# SCH_CubeNixie_2024-07-25.net
KiCad netlist of a schematic drawn in EasyEDA
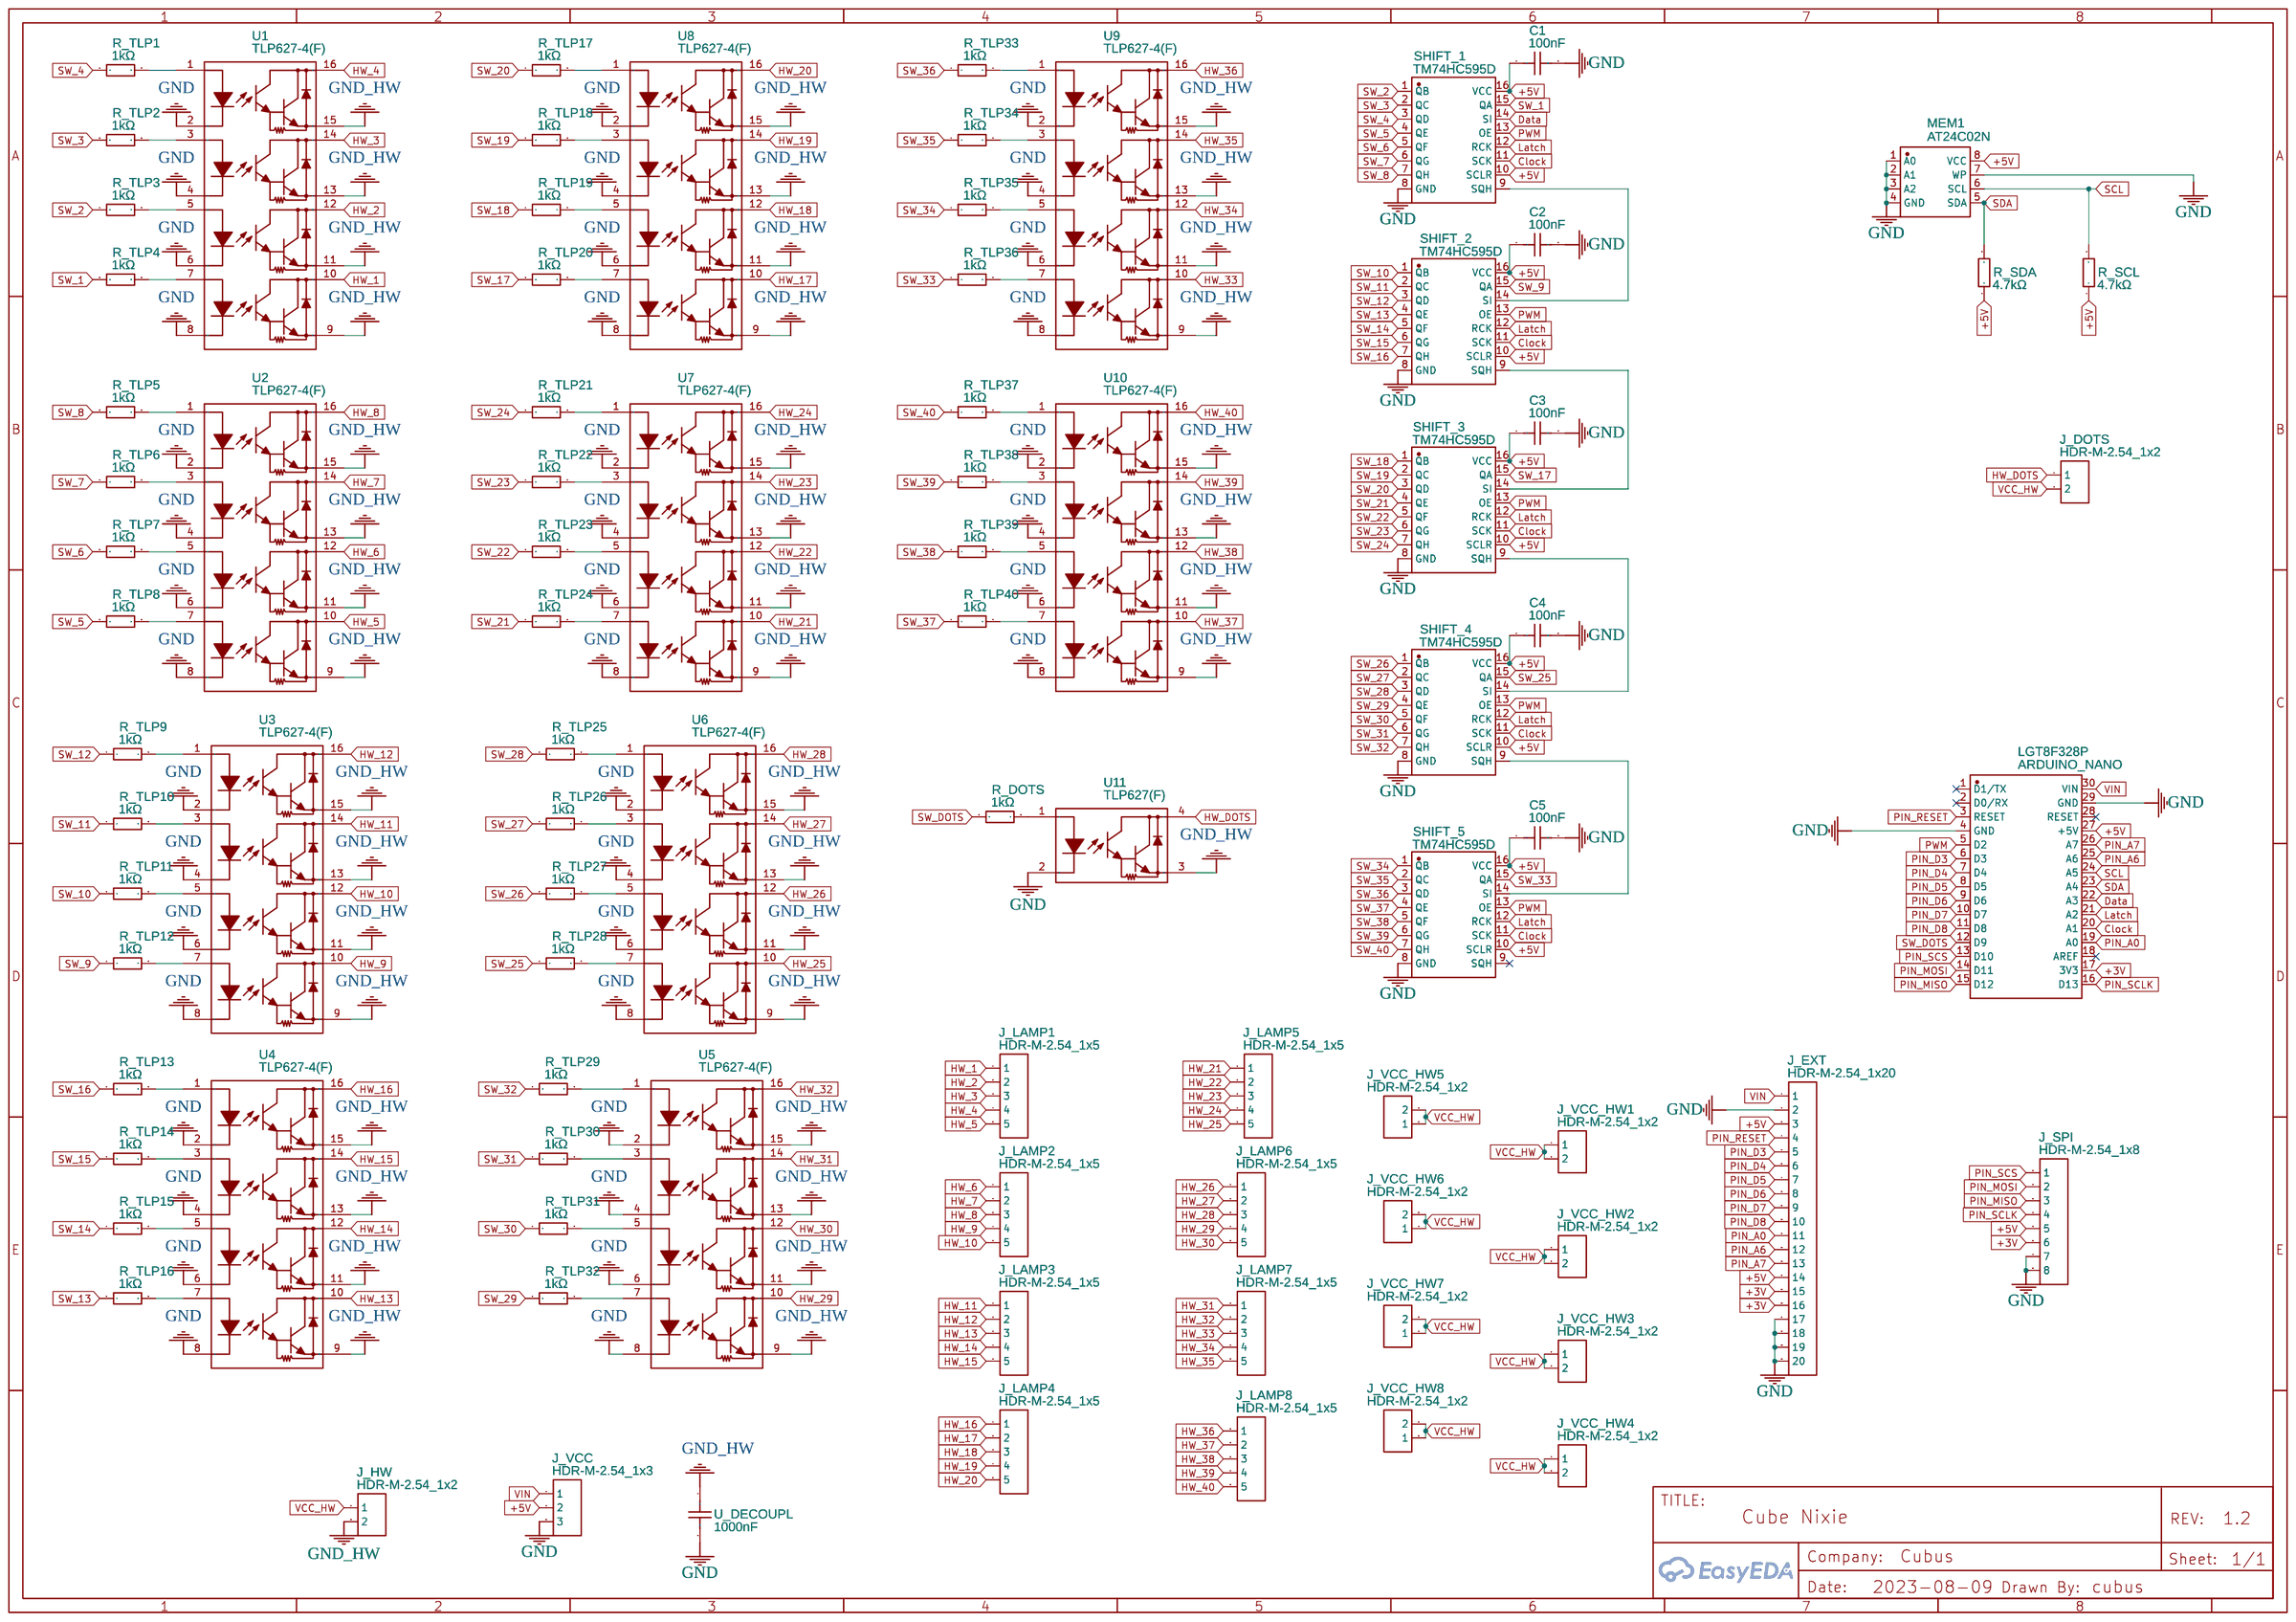
[diagram p0: schematic sheet]

(export (version "E")
  (design (tool "Eeschema 10.0.6"))
  (components
    (comp (ref "C1")
      (value "100nF")
      (fields (field (name "Manufacturer Part") "C3216X7R2A104M160AA") (field (name "Manufacturer") "TDK"))
      (libsource (lib "") (part "C3216X7R2A104M160AA"))
    )
    (comp (ref "C2")
      (value "100nF")
      (fields (field (name "Manufacturer Part") "C3216X7R2A104M160AA") (field (name "Manufacturer") "TDK"))
      (libsource (lib "") (part "C3216X7R2A104M160AA"))
    )
    (comp (ref "C3")
      (value "100nF")
      (fields (field (name "Manufacturer Part") "C3216X7R2A104M160AA") (field (name "Manufacturer") "TDK"))
      (libsource (lib "") (part "C3216X7R2A104M160AA"))
    )
    (comp (ref "C4")
      (value "100nF")
      (fields (field (name "Manufacturer Part") "C3216X7R2A104M160AA") (field (name "Manufacturer") "TDK"))
      (libsource (lib "") (part "C3216X7R2A104M160AA"))
    )
    (comp (ref "C5")
      (value "100nF")
      (fields (field (name "Manufacturer Part") "C3216X7R2A104M160AA") (field (name "Manufacturer") "TDK"))
      (libsource (lib "") (part "C3216X7R2A104M160AA"))
    )
    (comp (ref "J_DOTS") (value "HDR-M-2.54_1x2") (libsource (lib "") (part "HDR-M-2.54_1x2_3")))
    (comp (ref "J_EXT") (value "HDR-M-2.54_1x20") (libsource (lib "") (part "HDR-M-2.54_1x20")))
    (comp (ref "J_HW") (value "HDR-M-2.54_1x2") (libsource (lib "") (part "HDR-M-2.54_1x2_2")))
    (comp (ref "J_LAMP1") (value "HDR-M-2.54_1x5") (libsource (lib "") (part "HDR-M-2.54_1x5")))
    (comp (ref "J_LAMP2") (value "HDR-M-2.54_1x5") (libsource (lib "") (part "HDR-M-2.54_1x5")))
    (comp (ref "J_LAMP3") (value "HDR-M-2.54_1x5") (libsource (lib "") (part "HDR-M-2.54_1x5")))
    (comp (ref "J_LAMP4") (value "HDR-M-2.54_1x5") (libsource (lib "") (part "HDR-M-2.54_1x5")))
    (comp (ref "J_LAMP5") (value "HDR-M-2.54_1x5") (libsource (lib "") (part "HDR-M-2.54_1x5")))
    (comp (ref "J_LAMP6") (value "HDR-M-2.54_1x5") (libsource (lib "") (part "HDR-M-2.54_1x5")))
    (comp (ref "J_LAMP7") (value "HDR-M-2.54_1x5") (libsource (lib "") (part "HDR-M-2.54_1x5")))
    (comp (ref "J_LAMP8") (value "HDR-M-2.54_1x5") (libsource (lib "") (part "HDR-M-2.54_1x5")))
    (comp (ref "J_SPI") (value "HDR-M-2.54_1x8") (libsource (lib "") (part "HDR-M-2.54_1x8")))
    (comp (ref "J_VCC") (value "HDR-M-2.54_1x3") (libsource (lib "") (part "HDR-M-2.54_1x3")))
    (comp (ref "J_VCC_HW1") (value "HDR-M-2.54_1x2") (libsource (lib "") (part "HDR-M-2.54_1x2_1")))
    (comp (ref "J_VCC_HW2") (value "HDR-M-2.54_1x2") (libsource (lib "") (part "HDR-M-2.54_1x2_1")))
    (comp (ref "J_VCC_HW3") (value "HDR-M-2.54_1x2") (libsource (lib "") (part "HDR-M-2.54_1x2_1")))
    (comp (ref "J_VCC_HW4") (value "HDR-M-2.54_1x2") (libsource (lib "") (part "HDR-M-2.54_1x2_1")))
    (comp (ref "J_VCC_HW5") (value "HDR-M-2.54_1x2") (libsource (lib "") (part "HDR-M-2.54_1x2")))
    (comp (ref "J_VCC_HW6") (value "HDR-M-2.54_1x2") (libsource (lib "") (part "HDR-M-2.54_1x2")))
    (comp (ref "J_VCC_HW7") (value "HDR-M-2.54_1x2") (libsource (lib "") (part "HDR-M-2.54_1x2")))
    (comp (ref "J_VCC_HW8") (value "HDR-M-2.54_1x2") (libsource (lib "") (part "HDR-M-2.54_1x2")))
    (comp (ref "LGT8F328P") (value "ARDUINO_NANO") (libsource (lib "") (part "ARDUINO_NANO")))
    (comp (ref "MEM1")
      (value "AT24C02N")
      (fields (field (name "Manufacturer") "HGSEMI"))
      (libsource (lib "") (part "AT24C02N"))
    )
    (comp (ref "R_DOTS")
      (value "1kΩ")
      (fields (field (name "Manufacturer Part") "ERJ6ENF1001V") (field (name "Manufacturer") "PANASONIC(松下)"))
      (libsource (lib "") (part "ERJ-6ENF1001V_1"))
    )
    (comp (ref "R_SCL")
      (value "4.7kΩ")
      (fields (field (name "Manufacturer Part") "RMC04024K7JN") (field (name "Manufacturer") "Tyohm(幸亚电阻)"))
      (libsource (lib "") (part "RMC04024.7K5%N"))
    )
    (comp (ref "R_SDA")
      (value "4.7kΩ")
      (fields (field (name "Manufacturer Part") "RMC04024K7JN") (field (name "Manufacturer") "Tyohm(幸亚电阻)"))
      (libsource (lib "") (part "RMC04024.7K5%N_1"))
    )
    (comp (ref "R_TLP1")
      (value "1kΩ")
      (fields (field (name "Manufacturer Part") "ERJ6ENF1001V") (field (name "Manufacturer") "PANASONIC(松下)"))
      (libsource (lib "") (part "ERJ-6ENF1001V"))
    )
    (comp (ref "R_TLP2")
      (value "1kΩ")
      (fields (field (name "Manufacturer Part") "ERJ6ENF1001V") (field (name "Manufacturer") "PANASONIC(松下)"))
      (libsource (lib "") (part "ERJ-6ENF1001V"))
    )
    (comp (ref "R_TLP3")
      (value "1kΩ")
      (fields (field (name "Manufacturer Part") "ERJ6ENF1001V") (field (name "Manufacturer") "PANASONIC(松下)"))
      (libsource (lib "") (part "ERJ-6ENF1001V"))
    )
    (comp (ref "R_TLP4")
      (value "1kΩ")
      (fields (field (name "Manufacturer Part") "ERJ6ENF1001V") (field (name "Manufacturer") "PANASONIC(松下)"))
      (libsource (lib "") (part "ERJ-6ENF1001V"))
    )
    (comp (ref "R_TLP5")
      (value "1kΩ")
      (fields (field (name "Manufacturer Part") "ERJ6ENF1001V") (field (name "Manufacturer") "PANASONIC(松下)"))
      (libsource (lib "") (part "ERJ-6ENF1001V"))
    )
    (comp (ref "R_TLP6")
      (value "1kΩ")
      (fields (field (name "Manufacturer Part") "ERJ6ENF1001V") (field (name "Manufacturer") "PANASONIC(松下)"))
      (libsource (lib "") (part "ERJ-6ENF1001V"))
    )
    (comp (ref "R_TLP7")
      (value "1kΩ")
      (fields (field (name "Manufacturer Part") "ERJ6ENF1001V") (field (name "Manufacturer") "PANASONIC(松下)"))
      (libsource (lib "") (part "ERJ-6ENF1001V"))
    )
    (comp (ref "R_TLP8")
      (value "1kΩ")
      (fields (field (name "Manufacturer Part") "ERJ6ENF1001V") (field (name "Manufacturer") "PANASONIC(松下)"))
      (libsource (lib "") (part "ERJ-6ENF1001V"))
    )
    (comp (ref "R_TLP9")
      (value "1kΩ")
      (fields (field (name "Manufacturer Part") "ERJ6ENF1001V") (field (name "Manufacturer") "PANASONIC(松下)"))
      (libsource (lib "") (part "ERJ-6ENF1001V"))
    )
    (comp (ref "R_TLP10")
      (value "1kΩ")
      (fields (field (name "Manufacturer Part") "ERJ6ENF1001V") (field (name "Manufacturer") "PANASONIC(松下)"))
      (libsource (lib "") (part "ERJ-6ENF1001V"))
    )
    (comp (ref "R_TLP11")
      (value "1kΩ")
      (fields (field (name "Manufacturer Part") "ERJ6ENF1001V") (field (name "Manufacturer") "PANASONIC(松下)"))
      (libsource (lib "") (part "ERJ-6ENF1001V"))
    )
    (comp (ref "R_TLP12")
      (value "1kΩ")
      (fields (field (name "Manufacturer Part") "ERJ6ENF1001V") (field (name "Manufacturer") "PANASONIC(松下)"))
      (libsource (lib "") (part "ERJ-6ENF1001V"))
    )
    (comp (ref "R_TLP13")
      (value "1kΩ")
      (fields (field (name "Manufacturer Part") "ERJ6ENF1001V") (field (name "Manufacturer") "PANASONIC(松下)"))
      (libsource (lib "") (part "ERJ-6ENF1001V"))
    )
    (comp (ref "R_TLP14")
      (value "1kΩ")
      (fields (field (name "Manufacturer Part") "ERJ6ENF1001V") (field (name "Manufacturer") "PANASONIC(松下)"))
      (libsource (lib "") (part "ERJ-6ENF1001V"))
    )
    (comp (ref "R_TLP15")
      (value "1kΩ")
      (fields (field (name "Manufacturer Part") "ERJ6ENF1001V") (field (name "Manufacturer") "PANASONIC(松下)"))
      (libsource (lib "") (part "ERJ-6ENF1001V"))
    )
    (comp (ref "R_TLP16")
      (value "1kΩ")
      (fields (field (name "Manufacturer Part") "ERJ6ENF1001V") (field (name "Manufacturer") "PANASONIC(松下)"))
      (libsource (lib "") (part "ERJ-6ENF1001V"))
    )
    (comp (ref "R_TLP17")
      (value "1kΩ")
      (fields (field (name "Manufacturer Part") "ERJ6ENF1001V") (field (name "Manufacturer") "PANASONIC(松下)"))
      (libsource (lib "") (part "ERJ-6ENF1001V"))
    )
    (comp (ref "R_TLP18")
      (value "1kΩ")
      (fields (field (name "Manufacturer Part") "ERJ6ENF1001V") (field (name "Manufacturer") "PANASONIC(松下)"))
      (libsource (lib "") (part "ERJ-6ENF1001V"))
    )
    (comp (ref "R_TLP19")
      (value "1kΩ")
      (fields (field (name "Manufacturer Part") "ERJ6ENF1001V") (field (name "Manufacturer") "PANASONIC(松下)"))
      (libsource (lib "") (part "ERJ-6ENF1001V"))
    )
    (comp (ref "R_TLP20")
      (value "1kΩ")
      (fields (field (name "Manufacturer Part") "ERJ6ENF1001V") (field (name "Manufacturer") "PANASONIC(松下)"))
      (libsource (lib "") (part "ERJ-6ENF1001V"))
    )
    (comp (ref "R_TLP21")
      (value "1kΩ")
      (fields (field (name "Manufacturer Part") "ERJ6ENF1001V") (field (name "Manufacturer") "PANASONIC(松下)"))
      (libsource (lib "") (part "ERJ-6ENF1001V"))
    )
    (comp (ref "R_TLP22")
      (value "1kΩ")
      (fields (field (name "Manufacturer Part") "ERJ6ENF1001V") (field (name "Manufacturer") "PANASONIC(松下)"))
      (libsource (lib "") (part "ERJ-6ENF1001V"))
    )
    (comp (ref "R_TLP23")
      (value "1kΩ")
      (fields (field (name "Manufacturer Part") "ERJ6ENF1001V") (field (name "Manufacturer") "PANASONIC(松下)"))
      (libsource (lib "") (part "ERJ-6ENF1001V"))
    )
    (comp (ref "R_TLP24")
      (value "1kΩ")
      (fields (field (name "Manufacturer Part") "ERJ6ENF1001V") (field (name "Manufacturer") "PANASONIC(松下)"))
      (libsource (lib "") (part "ERJ-6ENF1001V"))
    )
    (comp (ref "R_TLP25")
      (value "1kΩ")
      (fields (field (name "Manufacturer Part") "ERJ6ENF1001V") (field (name "Manufacturer") "PANASONIC(松下)"))
      (libsource (lib "") (part "ERJ-6ENF1001V"))
    )
    (comp (ref "R_TLP26")
      (value "1kΩ")
      (fields (field (name "Manufacturer Part") "ERJ6ENF1001V") (field (name "Manufacturer") "PANASONIC(松下)"))
      (libsource (lib "") (part "ERJ-6ENF1001V"))
    )
    (comp (ref "R_TLP27")
      (value "1kΩ")
      (fields (field (name "Manufacturer Part") "ERJ6ENF1001V") (field (name "Manufacturer") "PANASONIC(松下)"))
      (libsource (lib "") (part "ERJ-6ENF1001V"))
    )
    (comp (ref "R_TLP28")
      (value "1kΩ")
      (fields (field (name "Manufacturer Part") "ERJ6ENF1001V") (field (name "Manufacturer") "PANASONIC(松下)"))
      (libsource (lib "") (part "ERJ-6ENF1001V"))
    )
    (comp (ref "R_TLP29")
      (value "1kΩ")
      (fields (field (name "Manufacturer Part") "ERJ6ENF1001V") (field (name "Manufacturer") "PANASONIC(松下)"))
      (libsource (lib "") (part "ERJ-6ENF1001V"))
    )
    (comp (ref "R_TLP30")
      (value "1kΩ")
      (fields (field (name "Manufacturer Part") "ERJ6ENF1001V") (field (name "Manufacturer") "PANASONIC(松下)"))
      (libsource (lib "") (part "ERJ-6ENF1001V"))
    )
    (comp (ref "R_TLP31")
      (value "1kΩ")
      (fields (field (name "Manufacturer Part") "ERJ6ENF1001V") (field (name "Manufacturer") "PANASONIC(松下)"))
      (libsource (lib "") (part "ERJ-6ENF1001V"))
    )
    (comp (ref "R_TLP32")
      (value "1kΩ")
      (fields (field (name "Manufacturer Part") "ERJ6ENF1001V") (field (name "Manufacturer") "PANASONIC(松下)"))
      (libsource (lib "") (part "ERJ-6ENF1001V"))
    )
    (comp (ref "R_TLP33")
      (value "1kΩ")
      (fields (field (name "Manufacturer Part") "ERJ6ENF1001V") (field (name "Manufacturer") "PANASONIC(松下)"))
      (libsource (lib "") (part "ERJ-6ENF1001V"))
    )
    (comp (ref "R_TLP34")
      (value "1kΩ")
      (fields (field (name "Manufacturer Part") "ERJ6ENF1001V") (field (name "Manufacturer") "PANASONIC(松下)"))
      (libsource (lib "") (part "ERJ-6ENF1001V"))
    )
    (comp (ref "R_TLP35")
      (value "1kΩ")
      (fields (field (name "Manufacturer Part") "ERJ6ENF1001V") (field (name "Manufacturer") "PANASONIC(松下)"))
      (libsource (lib "") (part "ERJ-6ENF1001V"))
    )
    (comp (ref "R_TLP36")
      (value "1kΩ")
      (fields (field (name "Manufacturer Part") "ERJ6ENF1001V") (field (name "Manufacturer") "PANASONIC(松下)"))
      (libsource (lib "") (part "ERJ-6ENF1001V"))
    )
    (comp (ref "R_TLP37")
      (value "1kΩ")
      (fields (field (name "Manufacturer Part") "ERJ6ENF1001V") (field (name "Manufacturer") "PANASONIC(松下)"))
      (libsource (lib "") (part "ERJ-6ENF1001V"))
    )
    (comp (ref "R_TLP38")
      (value "1kΩ")
      (fields (field (name "Manufacturer Part") "ERJ6ENF1001V") (field (name "Manufacturer") "PANASONIC(松下)"))
      (libsource (lib "") (part "ERJ-6ENF1001V"))
    )
    (comp (ref "R_TLP39")
      (value "1kΩ")
      (fields (field (name "Manufacturer Part") "ERJ6ENF1001V") (field (name "Manufacturer") "PANASONIC(松下)"))
      (libsource (lib "") (part "ERJ-6ENF1001V"))
    )
    (comp (ref "R_TLP40")
      (value "1kΩ")
      (fields (field (name "Manufacturer Part") "ERJ6ENF1001V") (field (name "Manufacturer") "PANASONIC(松下)"))
      (libsource (lib "") (part "ERJ-6ENF1001V"))
    )
    (comp (ref "SHIFT_1")
      (value "TM74HC595D")
      (fields (field (name "Manufacturer Part") "TM74HC595") (field (name "Manufacturer") "TM(天微)"))
      (libsource (lib "") (part "TM74HC595D"))
    )
    (comp (ref "SHIFT_2")
      (value "TM74HC595D")
      (fields (field (name "Manufacturer Part") "TM74HC595") (field (name "Manufacturer") "TM(天微)"))
      (libsource (lib "") (part "TM74HC595D"))
    )
    (comp (ref "SHIFT_3")
      (value "TM74HC595D")
      (fields (field (name "Manufacturer Part") "TM74HC595") (field (name "Manufacturer") "TM(天微)"))
      (libsource (lib "") (part "TM74HC595D"))
    )
    (comp (ref "SHIFT_4")
      (value "TM74HC595D")
      (fields (field (name "Manufacturer Part") "TM74HC595") (field (name "Manufacturer") "TM(天微)"))
      (libsource (lib "") (part "TM74HC595D"))
    )
    (comp (ref "SHIFT_5")
      (value "TM74HC595D")
      (fields (field (name "Manufacturer Part") "TM74HC595") (field (name "Manufacturer") "TM(天微)"))
      (libsource (lib "") (part "TM74HC595D"))
    )
    (comp (ref "U1")
      (value "TLP627-4(F)")
      (fields (field (name "Manufacturer") "TOSHIBA(东芝)"))
      (libsource (lib "") (part "TLP627-4(F)"))
    )
    (comp (ref "U2")
      (value "TLP627-4(F)")
      (fields (field (name "Manufacturer") "TOSHIBA(东芝)"))
      (libsource (lib "") (part "TLP627-4(F)"))
    )
    (comp (ref "U3")
      (value "TLP627-4(F)")
      (fields (field (name "Manufacturer") "TOSHIBA(东芝)"))
      (libsource (lib "") (part "TLP627-4(F)"))
    )
    (comp (ref "U4")
      (value "TLP627-4(F)")
      (fields (field (name "Manufacturer") "TOSHIBA(东芝)"))
      (libsource (lib "") (part "TLP627-4(F)"))
    )
    (comp (ref "U5")
      (value "TLP627-4(F)")
      (fields (field (name "Manufacturer") "TOSHIBA(东芝)"))
      (libsource (lib "") (part "TLP627-4(F)"))
    )
    (comp (ref "U6")
      (value "TLP627-4(F)")
      (fields (field (name "Manufacturer") "TOSHIBA(东芝)"))
      (libsource (lib "") (part "TLP627-4(F)"))
    )
    (comp (ref "U7")
      (value "TLP627-4(F)")
      (fields (field (name "Manufacturer") "TOSHIBA(东芝)"))
      (libsource (lib "") (part "TLP627-4(F)"))
    )
    (comp (ref "U8")
      (value "TLP627-4(F)")
      (fields (field (name "Manufacturer") "TOSHIBA(东芝)"))
      (libsource (lib "") (part "TLP627-4(F)"))
    )
    (comp (ref "U9")
      (value "TLP627-4(F)")
      (fields (field (name "Manufacturer") "TOSHIBA(东芝)"))
      (libsource (lib "") (part "TLP627-4(F)"))
    )
    (comp (ref "U10")
      (value "TLP627-4(F)")
      (fields (field (name "Manufacturer") "TOSHIBA(东芝)"))
      (libsource (lib "") (part "TLP627-4(F)"))
    )
    (comp (ref "U11")
      (value "TLP627(F)")
      (fields (field (name "Manufacturer") "TOSHIBA(东芝)"))
      (libsource (lib "") (part "TLP627(F)"))
    )
    (comp (ref "U_DECOUPL")
      (value "1000nF")
      (fields
        (field (name "Manufacturer Part") "CL21-0.1uF400V 5%")
        (field (name "Manufacturer") "Tongfeng(铜峰电子)")
      )
      (libsource (lib "") (part "CL21-0.1uF400V 5%"))
    )
  )
  (nets
    (net (code "1") (name "+3V") (class "Default")
      (node (ref "J_EXT") (pin "15") (pinfunction "15_15") (pintype "unspecified"))
      (node (ref "J_EXT") (pin "16") (pinfunction "16_16") (pintype "unspecified"))
      (node (ref "J_SPI") (pin "6") (pinfunction "6_6") (pintype "unspecified"))
      (node (ref "LGT8F328P") (pin "17") (pinfunction "3V3_17") (pintype "unspecified"))
    )
    (net (code "2") (name "+5V") (class "Default")
      (node (ref "C1") (pin "1") (pinfunction "1_1") (pintype "unspecified"))
      (node (ref "C2") (pin "1") (pinfunction "1_1") (pintype "unspecified"))
      (node (ref "C3") (pin "1") (pinfunction "1_1") (pintype "unspecified"))
      (node (ref "C4") (pin "1") (pinfunction "1_1") (pintype "unspecified"))
      (node (ref "C5") (pin "1") (pinfunction "1_1") (pintype "unspecified"))
      (node (ref "J_EXT") (pin "14") (pinfunction "14_14") (pintype "unspecified"))
      (node (ref "J_EXT") (pin "3") (pinfunction "3_3") (pintype "unspecified"))
      (node (ref "J_SPI") (pin "5") (pinfunction "5_5") (pintype "unspecified"))
      (node (ref "J_VCC") (pin "2") (pinfunction "2_2") (pintype "input"))
      (node (ref "LGT8F328P") (pin "27") (pinfunction "+5V_27") (pintype "unspecified"))
      (node (ref "MEM1") (pin "8") (pinfunction "VCC_8") (pintype "unspecified"))
      (node (ref "R_SCL") (pin "1") (pinfunction "1_1") (pintype "unspecified"))
      (node (ref "R_SDA") (pin "1") (pinfunction "1_1") (pintype "unspecified"))
      (node (ref "SHIFT_1") (pin "10") (pinfunction "SCLR_10") (pintype "unspecified"))
      (node (ref "SHIFT_1") (pin "16") (pinfunction "VCC_16") (pintype "unspecified"))
      (node (ref "SHIFT_2") (pin "10") (pinfunction "SCLR_10") (pintype "unspecified"))
      (node (ref "SHIFT_2") (pin "16") (pinfunction "VCC_16") (pintype "unspecified"))
      (node (ref "SHIFT_3") (pin "10") (pinfunction "SCLR_10") (pintype "unspecified"))
      (node (ref "SHIFT_3") (pin "16") (pinfunction "VCC_16") (pintype "unspecified"))
      (node (ref "SHIFT_4") (pin "10") (pinfunction "SCLR_10") (pintype "unspecified"))
      (node (ref "SHIFT_4") (pin "16") (pinfunction "VCC_16") (pintype "unspecified"))
      (node (ref "SHIFT_5") (pin "10") (pinfunction "SCLR_10") (pintype "unspecified"))
      (node (ref "SHIFT_5") (pin "16") (pinfunction "VCC_16") (pintype "unspecified"))
    )
    (net (code "3") (name "Clock") (class "Default")
      (node (ref "LGT8F328P") (pin "20") (pinfunction "A1_20") (pintype "unspecified"))
      (node (ref "SHIFT_1") (pin "11") (pinfunction "SCK_11") (pintype "unspecified"))
      (node (ref "SHIFT_2") (pin "11") (pinfunction "SCK_11") (pintype "unspecified"))
      (node (ref "SHIFT_3") (pin "11") (pinfunction "SCK_11") (pintype "unspecified"))
      (node (ref "SHIFT_4") (pin "11") (pinfunction "SCK_11") (pintype "unspecified"))
      (node (ref "SHIFT_5") (pin "11") (pinfunction "SCK_11") (pintype "unspecified"))
    )
    (net (code "4") (name "Data") (class "Default")
      (node (ref "LGT8F328P") (pin "22") (pinfunction "A3_22") (pintype "unspecified"))
      (node (ref "SHIFT_1") (pin "14") (pinfunction "SI_14") (pintype "unspecified"))
    )
    (net (code "5") (name "GND") (class "Default")
      (node (ref "C1") (pin "2") (pinfunction "2_2") (pintype "unspecified"))
      (node (ref "C2") (pin "2") (pinfunction "2_2") (pintype "unspecified"))
      (node (ref "C3") (pin "2") (pinfunction "2_2") (pintype "unspecified"))
      (node (ref "C4") (pin "2") (pinfunction "2_2") (pintype "unspecified"))
      (node (ref "C5") (pin "2") (pinfunction "2_2") (pintype "unspecified"))
      (node (ref "J_EXT") (pin "17") (pinfunction "17_17") (pintype "unspecified"))
      (node (ref "J_EXT") (pin "18") (pinfunction "18_18") (pintype "unspecified"))
      (node (ref "J_EXT") (pin "19") (pinfunction "19_19") (pintype "unspecified"))
      (node (ref "J_EXT") (pin "2") (pinfunction "2_2") (pintype "unspecified"))
      (node (ref "J_EXT") (pin "20") (pinfunction "20_20") (pintype "unspecified"))
      (node (ref "J_SPI") (pin "7") (pinfunction "7_7") (pintype "unspecified"))
      (node (ref "J_SPI") (pin "8") (pinfunction "8_8") (pintype "unspecified"))
      (node (ref "J_VCC") (pin "3") (pinfunction "3_3") (pintype "input"))
      (node (ref "LGT8F328P") (pin "29") (pinfunction "GND_29") (pintype "unspecified"))
      (node (ref "LGT8F328P") (pin "4") (pinfunction "GND_4") (pintype "unspecified"))
      (node (ref "MEM1") (pin "1") (pinfunction "A0_1") (pintype "unspecified"))
      (node (ref "MEM1") (pin "2") (pinfunction "A1_2") (pintype "unspecified"))
      (node (ref "MEM1") (pin "3") (pinfunction "A2_3") (pintype "unspecified"))
      (node (ref "MEM1") (pin "4") (pinfunction "GND_4") (pintype "unspecified"))
      (node (ref "MEM1") (pin "7") (pinfunction "WP_7") (pintype "unspecified"))
      (node (ref "SHIFT_1") (pin "8") (pinfunction "GND_8") (pintype "unspecified"))
      (node (ref "SHIFT_2") (pin "8") (pinfunction "GND_8") (pintype "unspecified"))
      (node (ref "SHIFT_3") (pin "8") (pinfunction "GND_8") (pintype "unspecified"))
      (node (ref "SHIFT_4") (pin "8") (pinfunction "GND_8") (pintype "unspecified"))
      (node (ref "SHIFT_5") (pin "8") (pinfunction "GND_8") (pintype "unspecified"))
      (node (ref "U1") (pin "2") (pinfunction "2_2") (pintype "unspecified"))
      (node (ref "U1") (pin "4") (pinfunction "4_4") (pintype "unspecified"))
      (node (ref "U1") (pin "6") (pinfunction "6_6") (pintype "unspecified"))
      (node (ref "U1") (pin "8") (pinfunction "8_8") (pintype "unspecified"))
      (node (ref "U10") (pin "2") (pinfunction "2_2") (pintype "unspecified"))
      (node (ref "U10") (pin "4") (pinfunction "4_4") (pintype "unspecified"))
      (node (ref "U10") (pin "6") (pinfunction "6_6") (pintype "unspecified"))
      (node (ref "U10") (pin "8") (pinfunction "8_8") (pintype "unspecified"))
      (node (ref "U11") (pin "2") (pinfunction "2_2") (pintype "unspecified"))
      (node (ref "U2") (pin "2") (pinfunction "2_2") (pintype "unspecified"))
      (node (ref "U2") (pin "4") (pinfunction "4_4") (pintype "unspecified"))
      (node (ref "U2") (pin "6") (pinfunction "6_6") (pintype "unspecified"))
      (node (ref "U2") (pin "8") (pinfunction "8_8") (pintype "unspecified"))
      (node (ref "U3") (pin "2") (pinfunction "2_2") (pintype "unspecified"))
      (node (ref "U3") (pin "4") (pinfunction "4_4") (pintype "unspecified"))
      (node (ref "U3") (pin "6") (pinfunction "6_6") (pintype "unspecified"))
      (node (ref "U3") (pin "8") (pinfunction "8_8") (pintype "unspecified"))
      (node (ref "U4") (pin "2") (pinfunction "2_2") (pintype "unspecified"))
      (node (ref "U4") (pin "4") (pinfunction "4_4") (pintype "unspecified"))
      (node (ref "U4") (pin "6") (pinfunction "6_6") (pintype "unspecified"))
      (node (ref "U4") (pin "8") (pinfunction "8_8") (pintype "unspecified"))
      (node (ref "U5") (pin "2") (pinfunction "2_2") (pintype "unspecified"))
      (node (ref "U5") (pin "4") (pinfunction "4_4") (pintype "unspecified"))
      (node (ref "U5") (pin "6") (pinfunction "6_6") (pintype "unspecified"))
      (node (ref "U5") (pin "8") (pinfunction "8_8") (pintype "unspecified"))
      (node (ref "U6") (pin "2") (pinfunction "2_2") (pintype "unspecified"))
      (node (ref "U6") (pin "4") (pinfunction "4_4") (pintype "unspecified"))
      (node (ref "U6") (pin "6") (pinfunction "6_6") (pintype "unspecified"))
      (node (ref "U6") (pin "8") (pinfunction "8_8") (pintype "unspecified"))
      (node (ref "U7") (pin "2") (pinfunction "2_2") (pintype "unspecified"))
      (node (ref "U7") (pin "4") (pinfunction "4_4") (pintype "unspecified"))
      (node (ref "U7") (pin "6") (pinfunction "6_6") (pintype "unspecified"))
      (node (ref "U7") (pin "8") (pinfunction "8_8") (pintype "unspecified"))
      (node (ref "U8") (pin "2") (pinfunction "2_2") (pintype "unspecified"))
      (node (ref "U8") (pin "4") (pinfunction "4_4") (pintype "unspecified"))
      (node (ref "U8") (pin "6") (pinfunction "6_6") (pintype "unspecified"))
      (node (ref "U8") (pin "8") (pinfunction "8_8") (pintype "unspecified"))
      (node (ref "U9") (pin "2") (pinfunction "2_2") (pintype "unspecified"))
      (node (ref "U9") (pin "4") (pinfunction "4_4") (pintype "unspecified"))
      (node (ref "U9") (pin "6") (pinfunction "6_6") (pintype "unspecified"))
      (node (ref "U9") (pin "8") (pinfunction "8_8") (pintype "unspecified"))
      (node (ref "U_DECOUPL") (pin "2") (pinfunction "2_2") (pintype "unspecified"))
    )
    (net (code "6") (name "GND_HW") (class "Default")
      (node (ref "J_HW") (pin "2") (pinfunction "2_2") (pintype "unspecified"))
      (node (ref "U1") (pin "11") (pinfunction "11_11") (pintype "unspecified"))
      (node (ref "U1") (pin "13") (pinfunction "13_13") (pintype "unspecified"))
      (node (ref "U1") (pin "15") (pinfunction "15_15") (pintype "unspecified"))
      (node (ref "U1") (pin "9") (pinfunction "9_9") (pintype "unspecified"))
      (node (ref "U10") (pin "11") (pinfunction "11_11") (pintype "unspecified"))
      (node (ref "U10") (pin "13") (pinfunction "13_13") (pintype "unspecified"))
      (node (ref "U10") (pin "15") (pinfunction "15_15") (pintype "unspecified"))
      (node (ref "U10") (pin "9") (pinfunction "9_9") (pintype "unspecified"))
      (node (ref "U11") (pin "3") (pinfunction "3_3") (pintype "unspecified"))
      (node (ref "U2") (pin "11") (pinfunction "11_11") (pintype "unspecified"))
      (node (ref "U2") (pin "13") (pinfunction "13_13") (pintype "unspecified"))
      (node (ref "U2") (pin "15") (pinfunction "15_15") (pintype "unspecified"))
      (node (ref "U2") (pin "9") (pinfunction "9_9") (pintype "unspecified"))
      (node (ref "U3") (pin "11") (pinfunction "11_11") (pintype "unspecified"))
      (node (ref "U3") (pin "13") (pinfunction "13_13") (pintype "unspecified"))
      (node (ref "U3") (pin "15") (pinfunction "15_15") (pintype "unspecified"))
      (node (ref "U3") (pin "9") (pinfunction "9_9") (pintype "unspecified"))
      (node (ref "U4") (pin "11") (pinfunction "11_11") (pintype "unspecified"))
      (node (ref "U4") (pin "13") (pinfunction "13_13") (pintype "unspecified"))
      (node (ref "U4") (pin "15") (pinfunction "15_15") (pintype "unspecified"))
      (node (ref "U4") (pin "9") (pinfunction "9_9") (pintype "unspecified"))
      (node (ref "U5") (pin "11") (pinfunction "11_11") (pintype "unspecified"))
      (node (ref "U5") (pin "13") (pinfunction "13_13") (pintype "unspecified"))
      (node (ref "U5") (pin "15") (pinfunction "15_15") (pintype "unspecified"))
      (node (ref "U5") (pin "9") (pinfunction "9_9") (pintype "unspecified"))
      (node (ref "U6") (pin "11") (pinfunction "11_11") (pintype "unspecified"))
      (node (ref "U6") (pin "13") (pinfunction "13_13") (pintype "unspecified"))
      (node (ref "U6") (pin "15") (pinfunction "15_15") (pintype "unspecified"))
      (node (ref "U6") (pin "9") (pinfunction "9_9") (pintype "unspecified"))
      (node (ref "U7") (pin "11") (pinfunction "11_11") (pintype "unspecified"))
      (node (ref "U7") (pin "13") (pinfunction "13_13") (pintype "unspecified"))
      (node (ref "U7") (pin "15") (pinfunction "15_15") (pintype "unspecified"))
      (node (ref "U7") (pin "9") (pinfunction "9_9") (pintype "unspecified"))
      (node (ref "U8") (pin "11") (pinfunction "11_11") (pintype "unspecified"))
      (node (ref "U8") (pin "13") (pinfunction "13_13") (pintype "unspecified"))
      (node (ref "U8") (pin "15") (pinfunction "15_15") (pintype "unspecified"))
      (node (ref "U8") (pin "9") (pinfunction "9_9") (pintype "unspecified"))
      (node (ref "U9") (pin "11") (pinfunction "11_11") (pintype "unspecified"))
      (node (ref "U9") (pin "13") (pinfunction "13_13") (pintype "unspecified"))
      (node (ref "U9") (pin "15") (pinfunction "15_15") (pintype "unspecified"))
      (node (ref "U9") (pin "9") (pinfunction "9_9") (pintype "unspecified"))
      (node (ref "U_DECOUPL") (pin "1") (pinfunction "1_1") (pintype "unspecified"))
    )
    (net (code "7") (name "HW_1") (class "Default")
      (node (ref "J_LAMP1") (pin "1") (pinfunction "1_1") (pintype "unspecified"))
      (node (ref "U1") (pin "10") (pinfunction "10_10") (pintype "unspecified"))
    )
    (net (code "8") (name "HW_2") (class "Default")
      (node (ref "J_LAMP1") (pin "2") (pinfunction "2_2") (pintype "unspecified"))
      (node (ref "U1") (pin "12") (pinfunction "12_12") (pintype "unspecified"))
    )
    (net (code "9") (name "HW_3") (class "Default")
      (node (ref "J_LAMP1") (pin "3") (pinfunction "3_3") (pintype "unspecified"))
      (node (ref "U1") (pin "14") (pinfunction "14_14") (pintype "unspecified"))
    )
    (net (code "10") (name "HW_4") (class "Default")
      (node (ref "J_LAMP1") (pin "4") (pinfunction "4_4") (pintype "unspecified"))
      (node (ref "U1") (pin "16") (pinfunction "16_16") (pintype "unspecified"))
    )
    (net (code "11") (name "HW_5") (class "Default")
      (node (ref "J_LAMP1") (pin "5") (pinfunction "5_5") (pintype "unspecified"))
      (node (ref "U2") (pin "10") (pinfunction "10_10") (pintype "unspecified"))
    )
    (net (code "12") (name "HW_6") (class "Default")
      (node (ref "J_LAMP2") (pin "1") (pinfunction "1_1") (pintype "unspecified"))
      (node (ref "U2") (pin "12") (pinfunction "12_12") (pintype "unspecified"))
    )
    (net (code "13") (name "HW_7") (class "Default")
      (node (ref "J_LAMP2") (pin "2") (pinfunction "2_2") (pintype "unspecified"))
      (node (ref "U2") (pin "14") (pinfunction "14_14") (pintype "unspecified"))
    )
    (net (code "14") (name "HW_8") (class "Default")
      (node (ref "J_LAMP2") (pin "3") (pinfunction "3_3") (pintype "unspecified"))
      (node (ref "U2") (pin "16") (pinfunction "16_16") (pintype "unspecified"))
    )
    (net (code "15") (name "HW_9") (class "Default")
      (node (ref "J_LAMP2") (pin "4") (pinfunction "4_4") (pintype "unspecified"))
      (node (ref "U3") (pin "10") (pinfunction "10_10") (pintype "unspecified"))
    )
    (net (code "16") (name "HW_10") (class "Default")
      (node (ref "J_LAMP2") (pin "5") (pinfunction "5_5") (pintype "unspecified"))
      (node (ref "U3") (pin "12") (pinfunction "12_12") (pintype "unspecified"))
    )
    (net (code "17") (name "HW_11") (class "Default")
      (node (ref "J_LAMP3") (pin "1") (pinfunction "1_1") (pintype "unspecified"))
      (node (ref "U3") (pin "14") (pinfunction "14_14") (pintype "unspecified"))
    )
    (net (code "18") (name "HW_12") (class "Default")
      (node (ref "J_LAMP3") (pin "2") (pinfunction "2_2") (pintype "unspecified"))
      (node (ref "U3") (pin "16") (pinfunction "16_16") (pintype "unspecified"))
    )
    (net (code "19") (name "HW_13") (class "Default")
      (node (ref "J_LAMP3") (pin "3") (pinfunction "3_3") (pintype "unspecified"))
      (node (ref "U4") (pin "10") (pinfunction "10_10") (pintype "unspecified"))
    )
    (net (code "20") (name "HW_14") (class "Default")
      (node (ref "J_LAMP3") (pin "4") (pinfunction "4_4") (pintype "unspecified"))
      (node (ref "U4") (pin "12") (pinfunction "12_12") (pintype "unspecified"))
    )
    (net (code "21") (name "HW_15") (class "Default")
      (node (ref "J_LAMP3") (pin "5") (pinfunction "5_5") (pintype "unspecified"))
      (node (ref "U4") (pin "14") (pinfunction "14_14") (pintype "unspecified"))
    )
    (net (code "22") (name "HW_16") (class "Default")
      (node (ref "J_LAMP4") (pin "1") (pinfunction "1_1") (pintype "unspecified"))
      (node (ref "U4") (pin "16") (pinfunction "16_16") (pintype "unspecified"))
    )
    (net (code "23") (name "HW_17") (class "Default")
      (node (ref "J_LAMP4") (pin "2") (pinfunction "2_2") (pintype "unspecified"))
      (node (ref "U8") (pin "10") (pinfunction "10_10") (pintype "unspecified"))
    )
    (net (code "24") (name "HW_18") (class "Default")
      (node (ref "J_LAMP4") (pin "3") (pinfunction "3_3") (pintype "unspecified"))
      (node (ref "U8") (pin "12") (pinfunction "12_12") (pintype "unspecified"))
    )
    (net (code "25") (name "HW_19") (class "Default")
      (node (ref "J_LAMP4") (pin "4") (pinfunction "4_4") (pintype "unspecified"))
      (node (ref "U8") (pin "14") (pinfunction "14_14") (pintype "unspecified"))
    )
    (net (code "26") (name "HW_20") (class "Default")
      (node (ref "J_LAMP4") (pin "5") (pinfunction "5_5") (pintype "unspecified"))
      (node (ref "U8") (pin "16") (pinfunction "16_16") (pintype "unspecified"))
    )
    (net (code "27") (name "HW_21") (class "Default")
      (node (ref "J_LAMP5") (pin "1") (pinfunction "1_1") (pintype "unspecified"))
      (node (ref "U7") (pin "10") (pinfunction "10_10") (pintype "unspecified"))
    )
    (net (code "28") (name "HW_22") (class "Default")
      (node (ref "J_LAMP5") (pin "2") (pinfunction "2_2") (pintype "unspecified"))
      (node (ref "U7") (pin "12") (pinfunction "12_12") (pintype "unspecified"))
    )
    (net (code "29") (name "HW_23") (class "Default")
      (node (ref "J_LAMP5") (pin "3") (pinfunction "3_3") (pintype "unspecified"))
      (node (ref "U7") (pin "14") (pinfunction "14_14") (pintype "unspecified"))
    )
    (net (code "30") (name "HW_24") (class "Default")
      (node (ref "J_LAMP5") (pin "4") (pinfunction "4_4") (pintype "unspecified"))
      (node (ref "U7") (pin "16") (pinfunction "16_16") (pintype "unspecified"))
    )
    (net (code "31") (name "HW_25") (class "Default")
      (node (ref "J_LAMP5") (pin "5") (pinfunction "5_5") (pintype "unspecified"))
      (node (ref "U6") (pin "10") (pinfunction "10_10") (pintype "unspecified"))
    )
    (net (code "32") (name "HW_26") (class "Default")
      (node (ref "J_LAMP6") (pin "1") (pinfunction "1_1") (pintype "unspecified"))
      (node (ref "U6") (pin "12") (pinfunction "12_12") (pintype "unspecified"))
    )
    (net (code "33") (name "HW_27") (class "Default")
      (node (ref "J_LAMP6") (pin "2") (pinfunction "2_2") (pintype "unspecified"))
      (node (ref "U6") (pin "14") (pinfunction "14_14") (pintype "unspecified"))
    )
    (net (code "34") (name "HW_28") (class "Default")
      (node (ref "J_LAMP6") (pin "3") (pinfunction "3_3") (pintype "unspecified"))
      (node (ref "U6") (pin "16") (pinfunction "16_16") (pintype "unspecified"))
    )
    (net (code "35") (name "HW_29") (class "Default")
      (node (ref "J_LAMP6") (pin "4") (pinfunction "4_4") (pintype "unspecified"))
      (node (ref "U5") (pin "10") (pinfunction "10_10") (pintype "unspecified"))
    )
    (net (code "36") (name "HW_30") (class "Default")
      (node (ref "J_LAMP6") (pin "5") (pinfunction "5_5") (pintype "unspecified"))
      (node (ref "U5") (pin "12") (pinfunction "12_12") (pintype "unspecified"))
    )
    (net (code "37") (name "HW_31") (class "Default")
      (node (ref "J_LAMP7") (pin "1") (pinfunction "1_1") (pintype "unspecified"))
      (node (ref "U5") (pin "14") (pinfunction "14_14") (pintype "unspecified"))
    )
    (net (code "38") (name "HW_32") (class "Default")
      (node (ref "J_LAMP7") (pin "2") (pinfunction "2_2") (pintype "unspecified"))
      (node (ref "U5") (pin "16") (pinfunction "16_16") (pintype "unspecified"))
    )
    (net (code "39") (name "HW_33") (class "Default")
      (node (ref "J_LAMP7") (pin "3") (pinfunction "3_3") (pintype "unspecified"))
      (node (ref "U9") (pin "10") (pinfunction "10_10") (pintype "unspecified"))
    )
    (net (code "40") (name "HW_34") (class "Default")
      (node (ref "J_LAMP7") (pin "4") (pinfunction "4_4") (pintype "unspecified"))
      (node (ref "U9") (pin "12") (pinfunction "12_12") (pintype "unspecified"))
    )
    (net (code "41") (name "HW_35") (class "Default")
      (node (ref "J_LAMP7") (pin "5") (pinfunction "5_5") (pintype "unspecified"))
      (node (ref "U9") (pin "14") (pinfunction "14_14") (pintype "unspecified"))
    )
    (net (code "42") (name "HW_36") (class "Default")
      (node (ref "J_LAMP8") (pin "1") (pinfunction "1_1") (pintype "unspecified"))
      (node (ref "U9") (pin "16") (pinfunction "16_16") (pintype "unspecified"))
    )
    (net (code "43") (name "HW_37") (class "Default")
      (node (ref "J_LAMP8") (pin "2") (pinfunction "2_2") (pintype "unspecified"))
      (node (ref "U10") (pin "10") (pinfunction "10_10") (pintype "unspecified"))
    )
    (net (code "44") (name "HW_38") (class "Default")
      (node (ref "J_LAMP8") (pin "3") (pinfunction "3_3") (pintype "unspecified"))
      (node (ref "U10") (pin "12") (pinfunction "12_12") (pintype "unspecified"))
    )
    (net (code "45") (name "HW_39") (class "Default")
      (node (ref "J_LAMP8") (pin "4") (pinfunction "4_4") (pintype "unspecified"))
      (node (ref "U10") (pin "14") (pinfunction "14_14") (pintype "unspecified"))
    )
    (net (code "46") (name "HW_40") (class "Default")
      (node (ref "J_LAMP8") (pin "5") (pinfunction "5_5") (pintype "unspecified"))
      (node (ref "U10") (pin "16") (pinfunction "16_16") (pintype "unspecified"))
    )
    (net (code "47") (name "HW_DOTS") (class "Default")
      (node (ref "J_DOTS") (pin "1") (pinfunction "1_1") (pintype "unspecified"))
      (node (ref "U11") (pin "4") (pinfunction "4_4") (pintype "unspecified"))
    )
    (net (code "48") (name "Latch") (class "Default")
      (node (ref "LGT8F328P") (pin "21") (pinfunction "A2_21") (pintype "unspecified"))
      (node (ref "SHIFT_1") (pin "12") (pinfunction "RCK_12") (pintype "unspecified"))
      (node (ref "SHIFT_2") (pin "12") (pinfunction "RCK_12") (pintype "unspecified"))
      (node (ref "SHIFT_3") (pin "12") (pinfunction "RCK_12") (pintype "unspecified"))
      (node (ref "SHIFT_4") (pin "12") (pinfunction "RCK_12") (pintype "unspecified"))
      (node (ref "SHIFT_5") (pin "12") (pinfunction "RCK_12") (pintype "unspecified"))
    )
    (net (code "49") (name "Net-(R_DOTS-Pad2)") (class "Default")
      (node (ref "R_DOTS") (pin "2") (pinfunction "2_2") (pintype "unspecified"))
      (node (ref "U11") (pin "1") (pinfunction "1_1") (pintype "unspecified"))
    )
    (net (code "50") (name "Net-(R_TLP1-Pad2)") (class "Default")
      (node (ref "R_TLP1") (pin "2") (pinfunction "2_2") (pintype "unspecified"))
      (node (ref "U1") (pin "1") (pinfunction "1_1") (pintype "unspecified"))
    )
    (net (code "51") (name "Net-(R_TLP2-Pad2)") (class "Default")
      (node (ref "R_TLP2") (pin "2") (pinfunction "2_2") (pintype "unspecified"))
      (node (ref "U1") (pin "3") (pinfunction "3_3") (pintype "unspecified"))
    )
    (net (code "52") (name "Net-(R_TLP3-Pad2)") (class "Default")
      (node (ref "R_TLP3") (pin "2") (pinfunction "2_2") (pintype "unspecified"))
      (node (ref "U1") (pin "5") (pinfunction "5_5") (pintype "unspecified"))
    )
    (net (code "53") (name "Net-(R_TLP4-Pad2)") (class "Default")
      (node (ref "R_TLP4") (pin "2") (pinfunction "2_2") (pintype "unspecified"))
      (node (ref "U1") (pin "7") (pinfunction "7_7") (pintype "unspecified"))
    )
    (net (code "54") (name "Net-(R_TLP5-Pad2)") (class "Default")
      (node (ref "R_TLP5") (pin "2") (pinfunction "2_2") (pintype "unspecified"))
      (node (ref "U2") (pin "1") (pinfunction "1_1") (pintype "unspecified"))
    )
    (net (code "55") (name "Net-(R_TLP6-Pad2)") (class "Default")
      (node (ref "R_TLP6") (pin "2") (pinfunction "2_2") (pintype "unspecified"))
      (node (ref "U2") (pin "3") (pinfunction "3_3") (pintype "unspecified"))
    )
    (net (code "56") (name "Net-(R_TLP7-Pad2)") (class "Default")
      (node (ref "R_TLP7") (pin "2") (pinfunction "2_2") (pintype "unspecified"))
      (node (ref "U2") (pin "5") (pinfunction "5_5") (pintype "unspecified"))
    )
    (net (code "57") (name "Net-(R_TLP8-Pad2)") (class "Default")
      (node (ref "R_TLP8") (pin "2") (pinfunction "2_2") (pintype "unspecified"))
      (node (ref "U2") (pin "7") (pinfunction "7_7") (pintype "unspecified"))
    )
    (net (code "58") (name "Net-(R_TLP9-Pad2)") (class "Default")
      (node (ref "R_TLP9") (pin "2") (pinfunction "2_2") (pintype "unspecified"))
      (node (ref "U3") (pin "1") (pinfunction "1_1") (pintype "unspecified"))
    )
    (net (code "59") (name "Net-(R_TLP10-Pad2)") (class "Default")
      (node (ref "R_TLP10") (pin "2") (pinfunction "2_2") (pintype "unspecified"))
      (node (ref "U3") (pin "3") (pinfunction "3_3") (pintype "unspecified"))
    )
    (net (code "60") (name "Net-(R_TLP11-Pad2)") (class "Default")
      (node (ref "R_TLP11") (pin "2") (pinfunction "2_2") (pintype "unspecified"))
      (node (ref "U3") (pin "5") (pinfunction "5_5") (pintype "unspecified"))
    )
    (net (code "61") (name "Net-(R_TLP12-Pad2)") (class "Default")
      (node (ref "R_TLP12") (pin "2") (pinfunction "2_2") (pintype "unspecified"))
      (node (ref "U3") (pin "7") (pinfunction "7_7") (pintype "unspecified"))
    )
    (net (code "62") (name "Net-(R_TLP13-Pad2)") (class "Default")
      (node (ref "R_TLP13") (pin "2") (pinfunction "2_2") (pintype "unspecified"))
      (node (ref "U4") (pin "1") (pinfunction "1_1") (pintype "unspecified"))
    )
    (net (code "63") (name "Net-(R_TLP14-Pad2)") (class "Default")
      (node (ref "R_TLP14") (pin "2") (pinfunction "2_2") (pintype "unspecified"))
      (node (ref "U4") (pin "3") (pinfunction "3_3") (pintype "unspecified"))
    )
    (net (code "64") (name "Net-(R_TLP15-Pad2)") (class "Default")
      (node (ref "R_TLP15") (pin "2") (pinfunction "2_2") (pintype "unspecified"))
      (node (ref "U4") (pin "5") (pinfunction "5_5") (pintype "unspecified"))
    )
    (net (code "65") (name "Net-(R_TLP16-Pad2)") (class "Default")
      (node (ref "R_TLP16") (pin "2") (pinfunction "2_2") (pintype "unspecified"))
      (node (ref "U4") (pin "7") (pinfunction "7_7") (pintype "unspecified"))
    )
    (net (code "66") (name "Net-(R_TLP17-Pad2)") (class "Default")
      (node (ref "R_TLP17") (pin "2") (pinfunction "2_2") (pintype "unspecified"))
      (node (ref "U8") (pin "1") (pinfunction "1_1") (pintype "unspecified"))
    )
    (net (code "67") (name "Net-(R_TLP18-Pad2)") (class "Default")
      (node (ref "R_TLP18") (pin "2") (pinfunction "2_2") (pintype "unspecified"))
      (node (ref "U8") (pin "3") (pinfunction "3_3") (pintype "unspecified"))
    )
    (net (code "68") (name "Net-(R_TLP19-Pad2)") (class "Default")
      (node (ref "R_TLP19") (pin "2") (pinfunction "2_2") (pintype "unspecified"))
      (node (ref "U8") (pin "5") (pinfunction "5_5") (pintype "unspecified"))
    )
    (net (code "69") (name "Net-(R_TLP20-Pad2)") (class "Default")
      (node (ref "R_TLP20") (pin "2") (pinfunction "2_2") (pintype "unspecified"))
      (node (ref "U8") (pin "7") (pinfunction "7_7") (pintype "unspecified"))
    )
    (net (code "70") (name "Net-(R_TLP21-Pad2)") (class "Default")
      (node (ref "R_TLP21") (pin "2") (pinfunction "2_2") (pintype "unspecified"))
      (node (ref "U7") (pin "1") (pinfunction "1_1") (pintype "unspecified"))
    )
    (net (code "71") (name "Net-(R_TLP22-Pad2)") (class "Default")
      (node (ref "R_TLP22") (pin "2") (pinfunction "2_2") (pintype "unspecified"))
      (node (ref "U7") (pin "3") (pinfunction "3_3") (pintype "unspecified"))
    )
    (net (code "72") (name "Net-(R_TLP23-Pad2)") (class "Default")
      (node (ref "R_TLP23") (pin "2") (pinfunction "2_2") (pintype "unspecified"))
      (node (ref "U7") (pin "5") (pinfunction "5_5") (pintype "unspecified"))
    )
    (net (code "73") (name "Net-(R_TLP24-Pad2)") (class "Default")
      (node (ref "R_TLP24") (pin "2") (pinfunction "2_2") (pintype "unspecified"))
      (node (ref "U7") (pin "7") (pinfunction "7_7") (pintype "unspecified"))
    )
    (net (code "74") (name "Net-(R_TLP25-Pad2)") (class "Default")
      (node (ref "R_TLP25") (pin "2") (pinfunction "2_2") (pintype "unspecified"))
      (node (ref "U6") (pin "1") (pinfunction "1_1") (pintype "unspecified"))
    )
    (net (code "75") (name "Net-(R_TLP26-Pad2)") (class "Default")
      (node (ref "R_TLP26") (pin "2") (pinfunction "2_2") (pintype "unspecified"))
      (node (ref "U6") (pin "3") (pinfunction "3_3") (pintype "unspecified"))
    )
    (net (code "76") (name "Net-(R_TLP27-Pad2)") (class "Default")
      (node (ref "R_TLP27") (pin "2") (pinfunction "2_2") (pintype "unspecified"))
      (node (ref "U6") (pin "5") (pinfunction "5_5") (pintype "unspecified"))
    )
    (net (code "77") (name "Net-(R_TLP28-Pad2)") (class "Default")
      (node (ref "R_TLP28") (pin "2") (pinfunction "2_2") (pintype "unspecified"))
      (node (ref "U6") (pin "7") (pinfunction "7_7") (pintype "unspecified"))
    )
    (net (code "78") (name "Net-(R_TLP29-Pad2)") (class "Default")
      (node (ref "R_TLP29") (pin "2") (pinfunction "2_2") (pintype "unspecified"))
      (node (ref "U5") (pin "1") (pinfunction "1_1") (pintype "unspecified"))
    )
    (net (code "79") (name "Net-(R_TLP30-Pad2)") (class "Default")
      (node (ref "R_TLP30") (pin "2") (pinfunction "2_2") (pintype "unspecified"))
      (node (ref "U5") (pin "3") (pinfunction "3_3") (pintype "unspecified"))
    )
    (net (code "80") (name "Net-(R_TLP31-Pad2)") (class "Default")
      (node (ref "R_TLP31") (pin "2") (pinfunction "2_2") (pintype "unspecified"))
      (node (ref "U5") (pin "5") (pinfunction "5_5") (pintype "unspecified"))
    )
    (net (code "81") (name "Net-(R_TLP32-Pad2)") (class "Default")
      (node (ref "R_TLP32") (pin "2") (pinfunction "2_2") (pintype "unspecified"))
      (node (ref "U5") (pin "7") (pinfunction "7_7") (pintype "unspecified"))
    )
    (net (code "82") (name "Net-(R_TLP33-Pad2)") (class "Default")
      (node (ref "R_TLP33") (pin "2") (pinfunction "2_2") (pintype "unspecified"))
      (node (ref "U9") (pin "1") (pinfunction "1_1") (pintype "unspecified"))
    )
    (net (code "83") (name "Net-(R_TLP34-Pad2)") (class "Default")
      (node (ref "R_TLP34") (pin "2") (pinfunction "2_2") (pintype "unspecified"))
      (node (ref "U9") (pin "3") (pinfunction "3_3") (pintype "unspecified"))
    )
    (net (code "84") (name "Net-(R_TLP35-Pad2)") (class "Default")
      (node (ref "R_TLP35") (pin "2") (pinfunction "2_2") (pintype "unspecified"))
      (node (ref "U9") (pin "5") (pinfunction "5_5") (pintype "unspecified"))
    )
    (net (code "85") (name "Net-(R_TLP36-Pad2)") (class "Default")
      (node (ref "R_TLP36") (pin "2") (pinfunction "2_2") (pintype "unspecified"))
      (node (ref "U9") (pin "7") (pinfunction "7_7") (pintype "unspecified"))
    )
    (net (code "86") (name "Net-(R_TLP37-Pad2)") (class "Default")
      (node (ref "R_TLP37") (pin "2") (pinfunction "2_2") (pintype "unspecified"))
      (node (ref "U10") (pin "1") (pinfunction "1_1") (pintype "unspecified"))
    )
    (net (code "87") (name "Net-(R_TLP38-Pad2)") (class "Default")
      (node (ref "R_TLP38") (pin "2") (pinfunction "2_2") (pintype "unspecified"))
      (node (ref "U10") (pin "3") (pinfunction "3_3") (pintype "unspecified"))
    )
    (net (code "88") (name "Net-(R_TLP39-Pad2)") (class "Default")
      (node (ref "R_TLP39") (pin "2") (pinfunction "2_2") (pintype "unspecified"))
      (node (ref "U10") (pin "5") (pinfunction "5_5") (pintype "unspecified"))
    )
    (net (code "89") (name "Net-(R_TLP40-Pad2)") (class "Default")
      (node (ref "R_TLP40") (pin "2") (pinfunction "2_2") (pintype "unspecified"))
      (node (ref "U10") (pin "7") (pinfunction "7_7") (pintype "unspecified"))
    )
    (net (code "90") (name "Net-(SHIFT_1-SQH)") (class "Default")
      (node (ref "SHIFT_1") (pin "9") (pinfunction "SQH_9") (pintype "unspecified"))
      (node (ref "SHIFT_2") (pin "14") (pinfunction "SI_14") (pintype "unspecified"))
    )
    (net (code "91") (name "Net-(SHIFT_2-SQH)") (class "Default")
      (node (ref "SHIFT_2") (pin "9") (pinfunction "SQH_9") (pintype "unspecified"))
      (node (ref "SHIFT_3") (pin "14") (pinfunction "SI_14") (pintype "unspecified"))
    )
    (net (code "92") (name "Net-(SHIFT_3-SQH)") (class "Default")
      (node (ref "SHIFT_3") (pin "9") (pinfunction "SQH_9") (pintype "unspecified"))
      (node (ref "SHIFT_4") (pin "14") (pinfunction "SI_14") (pintype "unspecified"))
    )
    (net (code "93") (name "Net-(SHIFT_4-SQH)") (class "Default")
      (node (ref "SHIFT_4") (pin "9") (pinfunction "SQH_9") (pintype "unspecified"))
      (node (ref "SHIFT_5") (pin "14") (pinfunction "SI_14") (pintype "unspecified"))
    )
    (net (code "94") (name "PIN_A0") (class "Default")
      (node (ref "J_EXT") (pin "11") (pinfunction "11_11") (pintype "unspecified"))
      (node (ref "LGT8F328P") (pin "19") (pinfunction "A0_19") (pintype "unspecified"))
    )
    (net (code "95") (name "PIN_A6") (class "Default")
      (node (ref "J_EXT") (pin "12") (pinfunction "12_12") (pintype "unspecified"))
      (node (ref "LGT8F328P") (pin "25") (pinfunction "A6_25") (pintype "unspecified"))
    )
    (net (code "96") (name "PIN_A7") (class "Default")
      (node (ref "J_EXT") (pin "13") (pinfunction "13_13") (pintype "unspecified"))
      (node (ref "LGT8F328P") (pin "26") (pinfunction "A7_26") (pintype "unspecified"))
    )
    (net (code "97") (name "PIN_D3") (class "Default")
      (node (ref "J_EXT") (pin "5") (pinfunction "5_5") (pintype "unspecified"))
      (node (ref "LGT8F328P") (pin "6") (pinfunction "D3_6") (pintype "unspecified"))
    )
    (net (code "98") (name "PIN_D4") (class "Default")
      (node (ref "J_EXT") (pin "6") (pinfunction "6_6") (pintype "unspecified"))
      (node (ref "LGT8F328P") (pin "7") (pinfunction "D4_7") (pintype "unspecified"))
    )
    (net (code "99") (name "PIN_D5") (class "Default")
      (node (ref "J_EXT") (pin "7") (pinfunction "7_7") (pintype "unspecified"))
      (node (ref "LGT8F328P") (pin "8") (pinfunction "D5_8") (pintype "unspecified"))
    )
    (net (code "100") (name "PIN_D6") (class "Default")
      (node (ref "J_EXT") (pin "8") (pinfunction "8_8") (pintype "unspecified"))
      (node (ref "LGT8F328P") (pin "9") (pinfunction "D6_9") (pintype "unspecified"))
    )
    (net (code "101") (name "PIN_D7") (class "Default")
      (node (ref "J_EXT") (pin "9") (pinfunction "9_9") (pintype "unspecified"))
      (node (ref "LGT8F328P") (pin "10") (pinfunction "D7_10") (pintype "unspecified"))
    )
    (net (code "102") (name "PIN_D8") (class "Default")
      (node (ref "J_EXT") (pin "10") (pinfunction "10_10") (pintype "unspecified"))
      (node (ref "LGT8F328P") (pin "11") (pinfunction "D8_11") (pintype "unspecified"))
    )
    (net (code "103") (name "PIN_MISO") (class "Default")
      (node (ref "J_SPI") (pin "3") (pinfunction "3_3") (pintype "unspecified"))
      (node (ref "LGT8F328P") (pin "15") (pinfunction "D12_15") (pintype "unspecified"))
    )
    (net (code "104") (name "PIN_MOSI") (class "Default")
      (node (ref "J_SPI") (pin "2") (pinfunction "2_2") (pintype "unspecified"))
      (node (ref "LGT8F328P") (pin "14") (pinfunction "D11_14") (pintype "unspecified"))
    )
    (net (code "105") (name "PIN_RESET") (class "Default")
      (node (ref "J_EXT") (pin "4") (pinfunction "4_4") (pintype "unspecified"))
      (node (ref "LGT8F328P") (pin "3") (pinfunction "RESET_3") (pintype "unspecified"))
    )
    (net (code "106") (name "PIN_SCLK") (class "Default")
      (node (ref "J_SPI") (pin "4") (pinfunction "4_4") (pintype "unspecified"))
      (node (ref "LGT8F328P") (pin "16") (pinfunction "D13_16") (pintype "unspecified"))
    )
    (net (code "107") (name "PIN_SCS") (class "Default")
      (node (ref "J_SPI") (pin "1") (pinfunction "1_1") (pintype "unspecified"))
      (node (ref "LGT8F328P") (pin "13") (pinfunction "D10_13") (pintype "unspecified"))
    )
    (net (code "108") (name "PWM") (class "Default")
      (node (ref "LGT8F328P") (pin "5") (pinfunction "D2_5") (pintype "unspecified"))
      (node (ref "SHIFT_1") (pin "13") (pinfunction "OE_13") (pintype "unspecified"))
      (node (ref "SHIFT_2") (pin "13") (pinfunction "OE_13") (pintype "unspecified"))
      (node (ref "SHIFT_3") (pin "13") (pinfunction "OE_13") (pintype "unspecified"))
      (node (ref "SHIFT_4") (pin "13") (pinfunction "OE_13") (pintype "unspecified"))
      (node (ref "SHIFT_5") (pin "13") (pinfunction "OE_13") (pintype "unspecified"))
    )
    (net (code "109") (name "SCL") (class "Default")
      (node (ref "LGT8F328P") (pin "24") (pinfunction "A5_24") (pintype "unspecified"))
      (node (ref "MEM1") (pin "6") (pinfunction "SCL_6") (pintype "unspecified"))
      (node (ref "R_SCL") (pin "2") (pinfunction "2_2") (pintype "unspecified"))
    )
    (net (code "110") (name "SDA") (class "Default")
      (node (ref "LGT8F328P") (pin "23") (pinfunction "A4_23") (pintype "unspecified"))
      (node (ref "MEM1") (pin "5") (pinfunction "SDA_5") (pintype "unspecified"))
      (node (ref "R_SDA") (pin "2") (pinfunction "2_2") (pintype "unspecified"))
    )
    (net (code "111") (name "SW_1") (class "Default")
      (node (ref "R_TLP4") (pin "1") (pinfunction "1_1") (pintype "unspecified"))
      (node (ref "SHIFT_1") (pin "15") (pinfunction "QA_15") (pintype "unspecified"))
    )
    (net (code "112") (name "SW_2") (class "Default")
      (node (ref "R_TLP3") (pin "1") (pinfunction "1_1") (pintype "unspecified"))
      (node (ref "SHIFT_1") (pin "1") (pinfunction "QB_1") (pintype "unspecified"))
    )
    (net (code "113") (name "SW_3") (class "Default")
      (node (ref "R_TLP2") (pin "1") (pinfunction "1_1") (pintype "unspecified"))
      (node (ref "SHIFT_1") (pin "2") (pinfunction "QC_2") (pintype "unspecified"))
    )
    (net (code "114") (name "SW_4") (class "Default")
      (node (ref "R_TLP1") (pin "1") (pinfunction "1_1") (pintype "unspecified"))
      (node (ref "SHIFT_1") (pin "3") (pinfunction "QD_3") (pintype "unspecified"))
    )
    (net (code "115") (name "SW_5") (class "Default")
      (node (ref "R_TLP8") (pin "1") (pinfunction "1_1") (pintype "unspecified"))
      (node (ref "SHIFT_1") (pin "4") (pinfunction "QE_4") (pintype "unspecified"))
    )
    (net (code "116") (name "SW_6") (class "Default")
      (node (ref "R_TLP7") (pin "1") (pinfunction "1_1") (pintype "unspecified"))
      (node (ref "SHIFT_1") (pin "5") (pinfunction "QF_5") (pintype "unspecified"))
    )
    (net (code "117") (name "SW_7") (class "Default")
      (node (ref "R_TLP6") (pin "1") (pinfunction "1_1") (pintype "unspecified"))
      (node (ref "SHIFT_1") (pin "6") (pinfunction "QG_6") (pintype "unspecified"))
    )
    (net (code "118") (name "SW_8") (class "Default")
      (node (ref "R_TLP5") (pin "1") (pinfunction "1_1") (pintype "unspecified"))
      (node (ref "SHIFT_1") (pin "7") (pinfunction "QH_7") (pintype "unspecified"))
    )
    (net (code "119") (name "SW_9") (class "Default")
      (node (ref "R_TLP12") (pin "1") (pinfunction "1_1") (pintype "unspecified"))
      (node (ref "SHIFT_2") (pin "15") (pinfunction "QA_15") (pintype "unspecified"))
    )
    (net (code "120") (name "SW_10") (class "Default")
      (node (ref "R_TLP11") (pin "1") (pinfunction "1_1") (pintype "unspecified"))
      (node (ref "SHIFT_2") (pin "1") (pinfunction "QB_1") (pintype "unspecified"))
    )
    (net (code "121") (name "SW_11") (class "Default")
      (node (ref "R_TLP10") (pin "1") (pinfunction "1_1") (pintype "unspecified"))
      (node (ref "SHIFT_2") (pin "2") (pinfunction "QC_2") (pintype "unspecified"))
    )
    (net (code "122") (name "SW_12") (class "Default")
      (node (ref "R_TLP9") (pin "1") (pinfunction "1_1") (pintype "unspecified"))
      (node (ref "SHIFT_2") (pin "3") (pinfunction "QD_3") (pintype "unspecified"))
    )
    (net (code "123") (name "SW_13") (class "Default")
      (node (ref "R_TLP16") (pin "1") (pinfunction "1_1") (pintype "unspecified"))
      (node (ref "SHIFT_2") (pin "4") (pinfunction "QE_4") (pintype "unspecified"))
    )
    (net (code "124") (name "SW_14") (class "Default")
      (node (ref "R_TLP15") (pin "1") (pinfunction "1_1") (pintype "unspecified"))
      (node (ref "SHIFT_2") (pin "5") (pinfunction "QF_5") (pintype "unspecified"))
    )
    (net (code "125") (name "SW_15") (class "Default")
      (node (ref "R_TLP14") (pin "1") (pinfunction "1_1") (pintype "unspecified"))
      (node (ref "SHIFT_2") (pin "6") (pinfunction "QG_6") (pintype "unspecified"))
    )
    (net (code "126") (name "SW_16") (class "Default")
      (node (ref "R_TLP13") (pin "1") (pinfunction "1_1") (pintype "unspecified"))
      (node (ref "SHIFT_2") (pin "7") (pinfunction "QH_7") (pintype "unspecified"))
    )
    (net (code "127") (name "SW_17") (class "Default")
      (node (ref "R_TLP20") (pin "1") (pinfunction "1_1") (pintype "unspecified"))
      (node (ref "SHIFT_3") (pin "15") (pinfunction "QA_15") (pintype "unspecified"))
    )
    (net (code "128") (name "SW_18") (class "Default")
      (node (ref "R_TLP19") (pin "1") (pinfunction "1_1") (pintype "unspecified"))
      (node (ref "SHIFT_3") (pin "1") (pinfunction "QB_1") (pintype "unspecified"))
    )
    (net (code "129") (name "SW_19") (class "Default")
      (node (ref "R_TLP18") (pin "1") (pinfunction "1_1") (pintype "unspecified"))
      (node (ref "SHIFT_3") (pin "2") (pinfunction "QC_2") (pintype "unspecified"))
    )
    (net (code "130") (name "SW_20") (class "Default")
      (node (ref "R_TLP17") (pin "1") (pinfunction "1_1") (pintype "unspecified"))
      (node (ref "SHIFT_3") (pin "3") (pinfunction "QD_3") (pintype "unspecified"))
    )
    (net (code "131") (name "SW_21") (class "Default")
      (node (ref "R_TLP24") (pin "1") (pinfunction "1_1") (pintype "unspecified"))
      (node (ref "SHIFT_3") (pin "4") (pinfunction "QE_4") (pintype "unspecified"))
    )
    (net (code "132") (name "SW_22") (class "Default")
      (node (ref "R_TLP23") (pin "1") (pinfunction "1_1") (pintype "unspecified"))
      (node (ref "SHIFT_3") (pin "5") (pinfunction "QF_5") (pintype "unspecified"))
    )
    (net (code "133") (name "SW_23") (class "Default")
      (node (ref "R_TLP22") (pin "1") (pinfunction "1_1") (pintype "unspecified"))
      (node (ref "SHIFT_3") (pin "6") (pinfunction "QG_6") (pintype "unspecified"))
    )
    (net (code "134") (name "SW_24") (class "Default")
      (node (ref "R_TLP21") (pin "1") (pinfunction "1_1") (pintype "unspecified"))
      (node (ref "SHIFT_3") (pin "7") (pinfunction "QH_7") (pintype "unspecified"))
    )
    (net (code "135") (name "SW_25") (class "Default")
      (node (ref "R_TLP28") (pin "1") (pinfunction "1_1") (pintype "unspecified"))
      (node (ref "SHIFT_4") (pin "15") (pinfunction "QA_15") (pintype "unspecified"))
    )
    (net (code "136") (name "SW_26") (class "Default")
      (node (ref "R_TLP27") (pin "1") (pinfunction "1_1") (pintype "unspecified"))
      (node (ref "SHIFT_4") (pin "1") (pinfunction "QB_1") (pintype "unspecified"))
    )
    (net (code "137") (name "SW_27") (class "Default")
      (node (ref "R_TLP26") (pin "1") (pinfunction "1_1") (pintype "unspecified"))
      (node (ref "SHIFT_4") (pin "2") (pinfunction "QC_2") (pintype "unspecified"))
    )
    (net (code "138") (name "SW_28") (class "Default")
      (node (ref "R_TLP25") (pin "1") (pinfunction "1_1") (pintype "unspecified"))
      (node (ref "SHIFT_4") (pin "3") (pinfunction "QD_3") (pintype "unspecified"))
    )
    (net (code "139") (name "SW_29") (class "Default")
      (node (ref "R_TLP32") (pin "1") (pinfunction "1_1") (pintype "unspecified"))
      (node (ref "SHIFT_4") (pin "4") (pinfunction "QE_4") (pintype "unspecified"))
    )
    (net (code "140") (name "SW_30") (class "Default")
      (node (ref "R_TLP31") (pin "1") (pinfunction "1_1") (pintype "unspecified"))
      (node (ref "SHIFT_4") (pin "5") (pinfunction "QF_5") (pintype "unspecified"))
    )
    (net (code "141") (name "SW_31") (class "Default")
      (node (ref "R_TLP30") (pin "1") (pinfunction "1_1") (pintype "unspecified"))
      (node (ref "SHIFT_4") (pin "6") (pinfunction "QG_6") (pintype "unspecified"))
    )
    (net (code "142") (name "SW_32") (class "Default")
      (node (ref "R_TLP29") (pin "1") (pinfunction "1_1") (pintype "unspecified"))
      (node (ref "SHIFT_4") (pin "7") (pinfunction "QH_7") (pintype "unspecified"))
    )
    (net (code "143") (name "SW_33") (class "Default")
      (node (ref "R_TLP36") (pin "1") (pinfunction "1_1") (pintype "unspecified"))
      (node (ref "SHIFT_5") (pin "15") (pinfunction "QA_15") (pintype "unspecified"))
    )
    (net (code "144") (name "SW_34") (class "Default")
      (node (ref "R_TLP35") (pin "1") (pinfunction "1_1") (pintype "unspecified"))
      (node (ref "SHIFT_5") (pin "1") (pinfunction "QB_1") (pintype "unspecified"))
    )
    (net (code "145") (name "SW_35") (class "Default")
      (node (ref "R_TLP34") (pin "1") (pinfunction "1_1") (pintype "unspecified"))
      (node (ref "SHIFT_5") (pin "2") (pinfunction "QC_2") (pintype "unspecified"))
    )
    (net (code "146") (name "SW_36") (class "Default")
      (node (ref "R_TLP33") (pin "1") (pinfunction "1_1") (pintype "unspecified"))
      (node (ref "SHIFT_5") (pin "3") (pinfunction "QD_3") (pintype "unspecified"))
    )
    (net (code "147") (name "SW_37") (class "Default")
      (node (ref "R_TLP40") (pin "1") (pinfunction "1_1") (pintype "unspecified"))
      (node (ref "SHIFT_5") (pin "4") (pinfunction "QE_4") (pintype "unspecified"))
    )
    (net (code "148") (name "SW_38") (class "Default")
      (node (ref "R_TLP39") (pin "1") (pinfunction "1_1") (pintype "unspecified"))
      (node (ref "SHIFT_5") (pin "5") (pinfunction "QF_5") (pintype "unspecified"))
    )
    (net (code "149") (name "SW_39") (class "Default")
      (node (ref "R_TLP38") (pin "1") (pinfunction "1_1") (pintype "unspecified"))
      (node (ref "SHIFT_5") (pin "6") (pinfunction "QG_6") (pintype "unspecified"))
    )
    (net (code "150") (name "SW_40") (class "Default")
      (node (ref "R_TLP37") (pin "1") (pinfunction "1_1") (pintype "unspecified"))
      (node (ref "SHIFT_5") (pin "7") (pinfunction "QH_7") (pintype "unspecified"))
    )
    (net (code "151") (name "SW_DOTS") (class "Default")
      (node (ref "LGT8F328P") (pin "12") (pinfunction "D9_12") (pintype "unspecified"))
      (node (ref "R_DOTS") (pin "1") (pinfunction "1_1") (pintype "unspecified"))
    )
    (net (code "152") (name "VCC_HW") (class "Default")
      (node (ref "J_DOTS") (pin "2") (pinfunction "2_2") (pintype "unspecified"))
      (node (ref "J_HW") (pin "1") (pinfunction "1_1") (pintype "unspecified"))
      (node (ref "J_VCC_HW1") (pin "1") (pinfunction "1_1") (pintype "unspecified"))
      (node (ref "J_VCC_HW1") (pin "2") (pinfunction "2_2") (pintype "unspecified"))
      (node (ref "J_VCC_HW2") (pin "1") (pinfunction "1_1") (pintype "unspecified"))
      (node (ref "J_VCC_HW2") (pin "2") (pinfunction "2_2") (pintype "unspecified"))
      (node (ref "J_VCC_HW3") (pin "1") (pinfunction "1_1") (pintype "unspecified"))
      (node (ref "J_VCC_HW3") (pin "2") (pinfunction "2_2") (pintype "unspecified"))
      (node (ref "J_VCC_HW4") (pin "1") (pinfunction "1_1") (pintype "unspecified"))
      (node (ref "J_VCC_HW4") (pin "2") (pinfunction "2_2") (pintype "unspecified"))
      (node (ref "J_VCC_HW5") (pin "1") (pinfunction "1_1") (pintype "unspecified"))
      (node (ref "J_VCC_HW5") (pin "2") (pinfunction "2_2") (pintype "unspecified"))
      (node (ref "J_VCC_HW6") (pin "1") (pinfunction "1_1") (pintype "unspecified"))
      (node (ref "J_VCC_HW6") (pin "2") (pinfunction "2_2") (pintype "unspecified"))
      (node (ref "J_VCC_HW7") (pin "1") (pinfunction "1_1") (pintype "unspecified"))
      (node (ref "J_VCC_HW7") (pin "2") (pinfunction "2_2") (pintype "unspecified"))
      (node (ref "J_VCC_HW8") (pin "1") (pinfunction "1_1") (pintype "unspecified"))
      (node (ref "J_VCC_HW8") (pin "2") (pinfunction "2_2") (pintype "unspecified"))
    )
    (net (code "153") (name "VIN") (class "Default")
      (node (ref "J_EXT") (pin "1") (pinfunction "1_1") (pintype "unspecified"))
      (node (ref "J_VCC") (pin "1") (pinfunction "1_1") (pintype "input"))
      (node (ref "LGT8F328P") (pin "30") (pinfunction "VIN_30") (pintype "unspecified"))
    )
    (net (code "154") (name "unconnected-(LGT8F328P-AREF-Pad18)") (class "Default")
      (node (ref "LGT8F328P") (pin "18") (pinfunction "AREF_18") (pintype "unspecified+no_connect"))
    )
    (net (code "155") (name "unconnected-(LGT8F328P-D0{slash}RX-Pad2)") (class "Default")
      (node (ref "LGT8F328P") (pin "2") (pinfunction "D0/RX_2") (pintype "unspecified+no_connect"))
    )
    (net (code "156") (name "unconnected-(LGT8F328P-D1{slash}TX-Pad1)") (class "Default")
      (node (ref "LGT8F328P") (pin "1") (pinfunction "D1/TX_1") (pintype "unspecified+no_connect"))
    )
    (net (code "157") (name "unconnected-(LGT8F328P-RESET-Pad28)") (class "Default")
      (node (ref "LGT8F328P") (pin "28") (pinfunction "RESET_28") (pintype "unspecified+no_connect"))
    )
    (net (code "158") (name "unconnected-(SHIFT_5-SQH-Pad9)") (class "Default")
      (node (ref "SHIFT_5") (pin "9") (pinfunction "SQH_9") (pintype "unspecified+no_connect"))
    )
  )
)
